# ET57.net
KiCad netlist of a schematic drawn in EAGLE
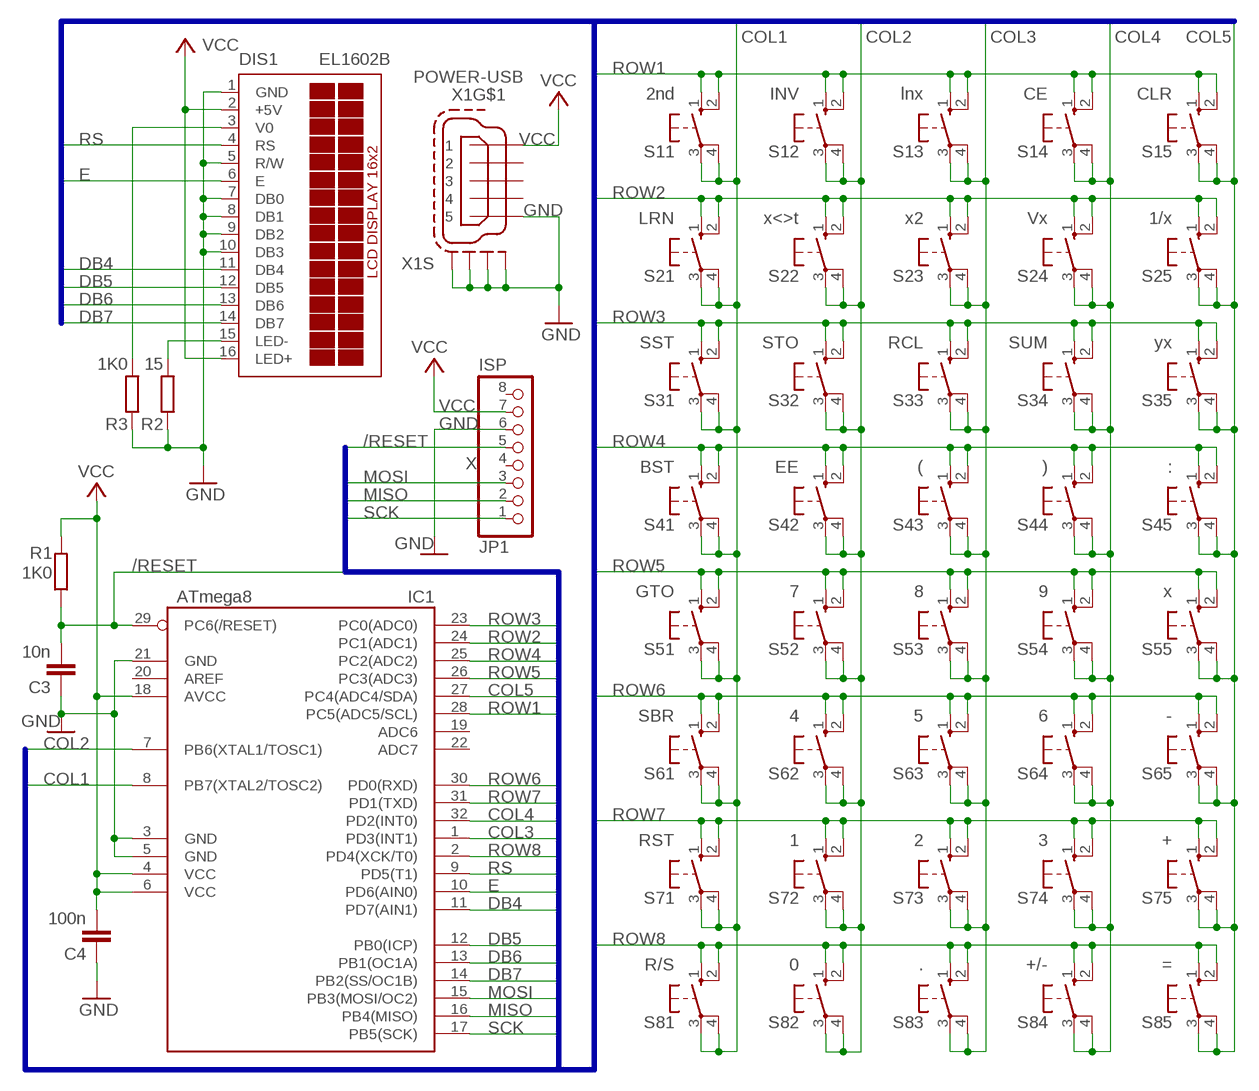
[diagram p0: schematic, sheet 1]

(export (version "E")
  (design (tool "Eeschema 10.0.6"))
  (components
    (comp (ref "C3")
      (value "10n")
      (footprint "eagle-import:C0805")
      (libsource (lib "eagle-import") (part "C-EUC0805"))
    )
    (comp (ref "C4")
      (value "100n")
      (footprint "eagle-import:C0805")
      (libsource (lib "eagle-import") (part "C-EUC0805"))
    )
    (comp (ref "DIS1")
      (value "EL1602B")
      (footprint "eagle-import:EL1602B")
      (libsource (lib "eagle-import") (part "EL1602B"))
    )
    (comp (ref "IC1")
      (value "ATmega8")
      (footprint "eagle-import:TQFP32-08")
      (fields (field (name "MPN") "ATMEGA8-16AU"))
      (libsource (lib "eagle-import") (part "MEGA8-AI"))
    )
    (comp (ref "JP1")
      (value "ISP")
      (footprint "eagle-import:1X08-BIG")
      (libsource (lib "eagle-import") (part "PINHD-1X8BIG"))
    )
    (comp (ref "R1")
      (value "1K0")
      (footprint "eagle-import:R0805")
      (libsource (lib "eagle-import") (part "R-EU_R0805"))
    )
    (comp (ref "R2")
      (value "15")
      (footprint "eagle-import:R0805")
      (libsource (lib "eagle-import") (part "R-EU_R0805"))
    )
    (comp (ref "R3")
      (value "1K0")
      (footprint "eagle-import:R0805")
      (libsource (lib "eagle-import") (part "R-EU_R0805"))
    )
    (comp (ref "S11")
      (value "2nd")
      (footprint "eagle-import:B3F-10XX")
      (fields (field (name "MPN") "B3F-1000"))
      (libsource (lib "eagle-import") (part "10-XX"))
    )
    (comp (ref "S12")
      (value "INV")
      (footprint "eagle-import:B3F-10XX")
      (fields (field (name "MPN") "B3F-1000"))
      (libsource (lib "eagle-import") (part "10-XX"))
    )
    (comp (ref "S13")
      (value "lnx")
      (footprint "eagle-import:B3F-10XX")
      (fields (field (name "MPN") "B3F-1000"))
      (libsource (lib "eagle-import") (part "10-XX"))
    )
    (comp (ref "S14")
      (value "CE")
      (footprint "eagle-import:B3F-10XX")
      (fields (field (name "MPN") "B3F-1000"))
      (libsource (lib "eagle-import") (part "10-XX"))
    )
    (comp (ref "S15")
      (value "CLR")
      (footprint "eagle-import:B3F-10XX")
      (fields (field (name "MPN") "B3F-1000"))
      (libsource (lib "eagle-import") (part "10-XX"))
    )
    (comp (ref "S21")
      (value "LRN")
      (footprint "eagle-import:B3F-10XX")
      (fields (field (name "MPN") "B3F-1000"))
      (libsource (lib "eagle-import") (part "10-XX"))
    )
    (comp (ref "S22")
      (value "x<>t")
      (footprint "eagle-import:B3F-10XX")
      (fields (field (name "MPN") "B3F-1000"))
      (libsource (lib "eagle-import") (part "10-XX"))
    )
    (comp (ref "S23")
      (value "x2")
      (footprint "eagle-import:B3F-10XX")
      (fields (field (name "MPN") "B3F-1000"))
      (libsource (lib "eagle-import") (part "10-XX"))
    )
    (comp (ref "S24")
      (value "Vx")
      (footprint "eagle-import:B3F-10XX")
      (fields (field (name "MPN") "B3F-1000"))
      (libsource (lib "eagle-import") (part "10-XX"))
    )
    (comp (ref "S25")
      (value "1/x")
      (footprint "eagle-import:B3F-10XX")
      (fields (field (name "MPN") "B3F-1000"))
      (libsource (lib "eagle-import") (part "10-XX"))
    )
    (comp (ref "S31")
      (value "SST")
      (footprint "eagle-import:B3F-10XX")
      (fields (field (name "MPN") "B3F-1000"))
      (libsource (lib "eagle-import") (part "10-XX"))
    )
    (comp (ref "S32")
      (value "STO")
      (footprint "eagle-import:B3F-10XX")
      (fields (field (name "MPN") "B3F-1000"))
      (libsource (lib "eagle-import") (part "10-XX"))
    )
    (comp (ref "S33")
      (value "RCL")
      (footprint "eagle-import:B3F-10XX")
      (fields (field (name "MPN") "B3F-1000"))
      (libsource (lib "eagle-import") (part "10-XX"))
    )
    (comp (ref "S34")
      (value "SUM")
      (footprint "eagle-import:B3F-10XX")
      (fields (field (name "MPN") "B3F-1000"))
      (libsource (lib "eagle-import") (part "10-XX"))
    )
    (comp (ref "S35")
      (value "yx")
      (footprint "eagle-import:B3F-10XX")
      (fields (field (name "MPN") "B3F-1000"))
      (libsource (lib "eagle-import") (part "10-XX"))
    )
    (comp (ref "S41")
      (value "BST")
      (footprint "eagle-import:B3F-10XX")
      (fields (field (name "MPN") "B3F-1000"))
      (libsource (lib "eagle-import") (part "10-XX"))
    )
    (comp (ref "S42")
      (value "EE")
      (footprint "eagle-import:B3F-10XX")
      (fields (field (name "MPN") "B3F-1000"))
      (libsource (lib "eagle-import") (part "10-XX"))
    )
    (comp (ref "S43")
      (value "(")
      (footprint "eagle-import:B3F-10XX")
      (fields (field (name "MPN") "B3F-1000"))
      (libsource (lib "eagle-import") (part "10-XX"))
    )
    (comp (ref "S44")
      (value ")")
      (footprint "eagle-import:B3F-10XX")
      (fields (field (name "MPN") "B3F-1000"))
      (libsource (lib "eagle-import") (part "10-XX"))
    )
    (comp (ref "S45")
      (value ":")
      (footprint "eagle-import:B3F-10XX")
      (fields (field (name "MPN") "B3F-1000"))
      (libsource (lib "eagle-import") (part "10-XX"))
    )
    (comp (ref "S51")
      (value "GTO")
      (footprint "eagle-import:B3F-10XX")
      (fields (field (name "MPN") "B3F-1000"))
      (libsource (lib "eagle-import") (part "10-XX"))
    )
    (comp (ref "S52")
      (value "7")
      (footprint "eagle-import:B3F-10XX")
      (fields (field (name "MPN") "B3F-1000"))
      (libsource (lib "eagle-import") (part "10-XX"))
    )
    (comp (ref "S53")
      (value "8")
      (footprint "eagle-import:B3F-10XX")
      (fields (field (name "MPN") "B3F-1000"))
      (libsource (lib "eagle-import") (part "10-XX"))
    )
    (comp (ref "S54")
      (value "9")
      (footprint "eagle-import:B3F-10XX")
      (fields (field (name "MPN") "B3F-1000"))
      (libsource (lib "eagle-import") (part "10-XX"))
    )
    (comp (ref "S55")
      (value "x")
      (footprint "eagle-import:B3F-10XX")
      (fields (field (name "MPN") "B3F-1000"))
      (libsource (lib "eagle-import") (part "10-XX"))
    )
    (comp (ref "S61")
      (value "SBR")
      (footprint "eagle-import:B3F-10XX")
      (fields (field (name "MPN") "B3F-1000"))
      (libsource (lib "eagle-import") (part "10-XX"))
    )
    (comp (ref "S62")
      (value "4")
      (footprint "eagle-import:B3F-10XX")
      (fields (field (name "MPN") "B3F-1000"))
      (libsource (lib "eagle-import") (part "10-XX"))
    )
    (comp (ref "S63")
      (value "5")
      (footprint "eagle-import:B3F-10XX")
      (fields (field (name "MPN") "B3F-1000"))
      (libsource (lib "eagle-import") (part "10-XX"))
    )
    (comp (ref "S64")
      (value "6")
      (footprint "eagle-import:B3F-10XX")
      (fields (field (name "MPN") "B3F-1000"))
      (libsource (lib "eagle-import") (part "10-XX"))
    )
    (comp (ref "S65")
      (value "-")
      (footprint "eagle-import:B3F-10XX")
      (fields (field (name "MPN") "B3F-1000"))
      (libsource (lib "eagle-import") (part "10-XX"))
    )
    (comp (ref "S71")
      (value "RST")
      (footprint "eagle-import:B3F-10XX")
      (fields (field (name "MPN") "B3F-1000"))
      (libsource (lib "eagle-import") (part "10-XX"))
    )
    (comp (ref "S72")
      (value "1")
      (footprint "eagle-import:B3F-10XX")
      (fields (field (name "MPN") "B3F-1000"))
      (libsource (lib "eagle-import") (part "10-XX"))
    )
    (comp (ref "S73")
      (value "2")
      (footprint "eagle-import:B3F-10XX")
      (fields (field (name "MPN") "B3F-1000"))
      (libsource (lib "eagle-import") (part "10-XX"))
    )
    (comp (ref "S74")
      (value "3")
      (footprint "eagle-import:B3F-10XX")
      (fields (field (name "MPN") "B3F-1000"))
      (libsource (lib "eagle-import") (part "10-XX"))
    )
    (comp (ref "S75")
      (value "+")
      (footprint "eagle-import:B3F-10XX")
      (fields (field (name "MPN") "B3F-1000"))
      (libsource (lib "eagle-import") (part "10-XX"))
    )
    (comp (ref "S81")
      (value "R/S")
      (footprint "eagle-import:B3F-10XX")
      (fields (field (name "MPN") "B3F-1000"))
      (libsource (lib "eagle-import") (part "10-XX"))
    )
    (comp (ref "S82")
      (value "0")
      (footprint "eagle-import:B3F-10XX")
      (fields (field (name "MPN") "B3F-1000"))
      (libsource (lib "eagle-import") (part "10-XX"))
    )
    (comp (ref "S83")
      (value ".")
      (footprint "eagle-import:B3F-10XX")
      (fields (field (name "MPN") "B3F-1000"))
      (libsource (lib "eagle-import") (part "10-XX"))
    )
    (comp (ref "S84")
      (value "+/-")
      (footprint "eagle-import:B3F-10XX")
      (fields (field (name "MPN") "B3F-1000"))
      (libsource (lib "eagle-import") (part "10-XX"))
    )
    (comp (ref "S85")
      (value "=")
      (footprint "eagle-import:B3F-10XX")
      (fields (field (name "MPN") "B3F-1000"))
      (libsource (lib "eagle-import") (part "10-XX"))
    )
    (comp (ref "X1")
      (value "POWER-USB")
      (footprint "eagle-import:32005-201")
      (libsource (lib "eagle-import") (part "MINI-USB-SCHIELD-32005-201"))
    )
  )
  (nets
    (net (code "1") (name "/COL1") (class "Default")
      (node (ref "IC1") (pin "8") (pinfunction "PB7(XTAL2/TOSC2)_8") (pintype "bidirectional"))
      (node (ref "S11") (pin "3") (pinfunction "P_3") (pintype "passive"))
      (node (ref "S11") (pin "4") (pinfunction "P1_4") (pintype "passive"))
      (node (ref "S21") (pin "3") (pinfunction "P_3") (pintype "passive"))
      (node (ref "S21") (pin "4") (pinfunction "P1_4") (pintype "passive"))
      (node (ref "S31") (pin "3") (pinfunction "P_3") (pintype "passive"))
      (node (ref "S31") (pin "4") (pinfunction "P1_4") (pintype "passive"))
      (node (ref "S41") (pin "3") (pinfunction "P_3") (pintype "passive"))
      (node (ref "S41") (pin "4") (pinfunction "P1_4") (pintype "passive"))
      (node (ref "S51") (pin "3") (pinfunction "P_3") (pintype "passive"))
      (node (ref "S51") (pin "4") (pinfunction "P1_4") (pintype "passive"))
      (node (ref "S61") (pin "3") (pinfunction "P_3") (pintype "passive"))
      (node (ref "S61") (pin "4") (pinfunction "P1_4") (pintype "passive"))
      (node (ref "S71") (pin "3") (pinfunction "P_3") (pintype "passive"))
      (node (ref "S71") (pin "4") (pinfunction "P1_4") (pintype "passive"))
      (node (ref "S81") (pin "3") (pinfunction "P_3") (pintype "passive"))
      (node (ref "S81") (pin "4") (pinfunction "P1_4") (pintype "passive"))
    )
    (net (code "2") (name "/COL2") (class "Default")
      (node (ref "IC1") (pin "7") (pinfunction "PB6(XTAL1/TOSC1)_7") (pintype "bidirectional"))
      (node (ref "S12") (pin "3") (pinfunction "P_3") (pintype "passive"))
      (node (ref "S12") (pin "4") (pinfunction "P1_4") (pintype "passive"))
      (node (ref "S22") (pin "3") (pinfunction "P_3") (pintype "passive"))
      (node (ref "S22") (pin "4") (pinfunction "P1_4") (pintype "passive"))
      (node (ref "S32") (pin "3") (pinfunction "P_3") (pintype "passive"))
      (node (ref "S32") (pin "4") (pinfunction "P1_4") (pintype "passive"))
      (node (ref "S42") (pin "3") (pinfunction "P_3") (pintype "passive"))
      (node (ref "S42") (pin "4") (pinfunction "P1_4") (pintype "passive"))
      (node (ref "S52") (pin "3") (pinfunction "P_3") (pintype "passive"))
      (node (ref "S52") (pin "4") (pinfunction "P1_4") (pintype "passive"))
      (node (ref "S62") (pin "3") (pinfunction "P_3") (pintype "passive"))
      (node (ref "S62") (pin "4") (pinfunction "P1_4") (pintype "passive"))
      (node (ref "S72") (pin "3") (pinfunction "P_3") (pintype "passive"))
      (node (ref "S72") (pin "4") (pinfunction "P1_4") (pintype "passive"))
      (node (ref "S82") (pin "3") (pinfunction "P_3") (pintype "passive"))
      (node (ref "S82") (pin "4") (pinfunction "P1_4") (pintype "passive"))
    )
    (net (code "3") (name "/COL3") (class "Default")
      (node (ref "IC1") (pin "1") (pinfunction "PD3(INT1)_1") (pintype "bidirectional"))
      (node (ref "S13") (pin "3") (pinfunction "P_3") (pintype "passive"))
      (node (ref "S13") (pin "4") (pinfunction "P1_4") (pintype "passive"))
      (node (ref "S23") (pin "3") (pinfunction "P_3") (pintype "passive"))
      (node (ref "S23") (pin "4") (pinfunction "P1_4") (pintype "passive"))
      (node (ref "S33") (pin "3") (pinfunction "P_3") (pintype "passive"))
      (node (ref "S33") (pin "4") (pinfunction "P1_4") (pintype "passive"))
      (node (ref "S43") (pin "3") (pinfunction "P_3") (pintype "passive"))
      (node (ref "S43") (pin "4") (pinfunction "P1_4") (pintype "passive"))
      (node (ref "S53") (pin "3") (pinfunction "P_3") (pintype "passive"))
      (node (ref "S53") (pin "4") (pinfunction "P1_4") (pintype "passive"))
      (node (ref "S63") (pin "3") (pinfunction "P_3") (pintype "passive"))
      (node (ref "S63") (pin "4") (pinfunction "P1_4") (pintype "passive"))
      (node (ref "S73") (pin "3") (pinfunction "P_3") (pintype "passive"))
      (node (ref "S73") (pin "4") (pinfunction "P1_4") (pintype "passive"))
      (node (ref "S83") (pin "3") (pinfunction "P_3") (pintype "passive"))
      (node (ref "S83") (pin "4") (pinfunction "P1_4") (pintype "passive"))
    )
    (net (code "4") (name "/COL4") (class "Default")
      (node (ref "IC1") (pin "32") (pinfunction "PD2(INT0)_32") (pintype "bidirectional"))
      (node (ref "S14") (pin "3") (pinfunction "P_3") (pintype "passive"))
      (node (ref "S14") (pin "4") (pinfunction "P1_4") (pintype "passive"))
      (node (ref "S24") (pin "3") (pinfunction "P_3") (pintype "passive"))
      (node (ref "S24") (pin "4") (pinfunction "P1_4") (pintype "passive"))
      (node (ref "S34") (pin "3") (pinfunction "P_3") (pintype "passive"))
      (node (ref "S34") (pin "4") (pinfunction "P1_4") (pintype "passive"))
      (node (ref "S44") (pin "3") (pinfunction "P_3") (pintype "passive"))
      (node (ref "S44") (pin "4") (pinfunction "P1_4") (pintype "passive"))
      (node (ref "S54") (pin "3") (pinfunction "P_3") (pintype "passive"))
      (node (ref "S54") (pin "4") (pinfunction "P1_4") (pintype "passive"))
      (node (ref "S64") (pin "3") (pinfunction "P_3") (pintype "passive"))
      (node (ref "S64") (pin "4") (pinfunction "P1_4") (pintype "passive"))
      (node (ref "S74") (pin "3") (pinfunction "P_3") (pintype "passive"))
      (node (ref "S74") (pin "4") (pinfunction "P1_4") (pintype "passive"))
      (node (ref "S84") (pin "3") (pinfunction "P_3") (pintype "passive"))
      (node (ref "S84") (pin "4") (pinfunction "P1_4") (pintype "passive"))
    )
    (net (code "5") (name "/COL5") (class "Default")
      (node (ref "IC1") (pin "27") (pinfunction "PC4(ADC4/SDA)_27") (pintype "bidirectional"))
      (node (ref "S15") (pin "3") (pinfunction "P_3") (pintype "passive"))
      (node (ref "S15") (pin "4") (pinfunction "P1_4") (pintype "passive"))
      (node (ref "S25") (pin "3") (pinfunction "P_3") (pintype "passive"))
      (node (ref "S25") (pin "4") (pinfunction "P1_4") (pintype "passive"))
      (node (ref "S35") (pin "3") (pinfunction "P_3") (pintype "passive"))
      (node (ref "S35") (pin "4") (pinfunction "P1_4") (pintype "passive"))
      (node (ref "S45") (pin "3") (pinfunction "P_3") (pintype "passive"))
      (node (ref "S45") (pin "4") (pinfunction "P1_4") (pintype "passive"))
      (node (ref "S55") (pin "3") (pinfunction "P_3") (pintype "passive"))
      (node (ref "S55") (pin "4") (pinfunction "P1_4") (pintype "passive"))
      (node (ref "S65") (pin "3") (pinfunction "P_3") (pintype "passive"))
      (node (ref "S65") (pin "4") (pinfunction "P1_4") (pintype "passive"))
      (node (ref "S75") (pin "3") (pinfunction "P_3") (pintype "passive"))
      (node (ref "S75") (pin "4") (pinfunction "P1_4") (pintype "passive"))
      (node (ref "S85") (pin "3") (pinfunction "P_3") (pintype "passive"))
      (node (ref "S85") (pin "4") (pinfunction "P1_4") (pintype "passive"))
    )
    (net (code "6") (name "/DB4") (class "Default")
      (node (ref "DIS1") (pin "11") (pinfunction "DB4_11") (pintype "input"))
      (node (ref "IC1") (pin "11") (pinfunction "PD7(AIN1)_11") (pintype "bidirectional"))
    )
    (net (code "7") (name "/DB5") (class "Default")
      (node (ref "DIS1") (pin "12") (pinfunction "DB5_12") (pintype "input"))
      (node (ref "IC1") (pin "12") (pinfunction "PB0(ICP)_12") (pintype "bidirectional"))
    )
    (net (code "8") (name "/DB6") (class "Default")
      (node (ref "DIS1") (pin "13") (pinfunction "DB6_13") (pintype "input"))
      (node (ref "IC1") (pin "13") (pinfunction "PB1(OC1A)_13") (pintype "bidirectional"))
    )
    (net (code "9") (name "/DB7") (class "Default")
      (node (ref "DIS1") (pin "14") (pinfunction "DB7_14") (pintype "input"))
      (node (ref "IC1") (pin "14") (pinfunction "PB2(SS/OC1B)_14") (pintype "bidirectional"))
    )
    (net (code "10") (name "/E") (class "Default")
      (node (ref "DIS1") (pin "6") (pinfunction "E_6") (pintype "input"))
      (node (ref "IC1") (pin "10") (pinfunction "PD6(AIN0)_10") (pintype "bidirectional"))
    )
    (net (code "11") (name "/MISO") (class "Default")
      (node (ref "IC1") (pin "16") (pinfunction "PB4(MISO)_16") (pintype "bidirectional"))
      (node (ref "JP1") (pin "2") (pinfunction "2_2") (pintype "passive"))
    )
    (net (code "12") (name "/MOSI") (class "Default")
      (node (ref "IC1") (pin "15") (pinfunction "PB3(MOSI/OC2)_15") (pintype "bidirectional"))
      (node (ref "JP1") (pin "3") (pinfunction "3_3") (pintype "passive"))
    )
    (net (code "13") (name "/ROW1") (class "Default")
      (node (ref "IC1") (pin "28") (pinfunction "PC5(ADC5/SCL)_28") (pintype "bidirectional"))
      (node (ref "S11") (pin "1") (pinfunction "S_1") (pintype "passive"))
      (node (ref "S11") (pin "2") (pinfunction "S1_2") (pintype "passive"))
      (node (ref "S12") (pin "1") (pinfunction "S_1") (pintype "passive"))
      (node (ref "S12") (pin "2") (pinfunction "S1_2") (pintype "passive"))
      (node (ref "S13") (pin "1") (pinfunction "S_1") (pintype "passive"))
      (node (ref "S13") (pin "2") (pinfunction "S1_2") (pintype "passive"))
      (node (ref "S14") (pin "1") (pinfunction "S_1") (pintype "passive"))
      (node (ref "S14") (pin "2") (pinfunction "S1_2") (pintype "passive"))
      (node (ref "S15") (pin "1") (pinfunction "S_1") (pintype "passive"))
      (node (ref "S15") (pin "2") (pinfunction "S1_2") (pintype "passive"))
    )
    (net (code "14") (name "/ROW2") (class "Default")
      (node (ref "IC1") (pin "24") (pinfunction "PC1(ADC1)_24") (pintype "bidirectional"))
      (node (ref "S21") (pin "1") (pinfunction "S_1") (pintype "passive"))
      (node (ref "S21") (pin "2") (pinfunction "S1_2") (pintype "passive"))
      (node (ref "S22") (pin "1") (pinfunction "S_1") (pintype "passive"))
      (node (ref "S22") (pin "2") (pinfunction "S1_2") (pintype "passive"))
      (node (ref "S23") (pin "1") (pinfunction "S_1") (pintype "passive"))
      (node (ref "S23") (pin "2") (pinfunction "S1_2") (pintype "passive"))
      (node (ref "S24") (pin "1") (pinfunction "S_1") (pintype "passive"))
      (node (ref "S24") (pin "2") (pinfunction "S1_2") (pintype "passive"))
      (node (ref "S25") (pin "1") (pinfunction "S_1") (pintype "passive"))
      (node (ref "S25") (pin "2") (pinfunction "S1_2") (pintype "passive"))
    )
    (net (code "15") (name "/ROW3") (class "Default")
      (node (ref "IC1") (pin "23") (pinfunction "PC0(ADC0)_23") (pintype "bidirectional"))
      (node (ref "S31") (pin "1") (pinfunction "S_1") (pintype "passive"))
      (node (ref "S31") (pin "2") (pinfunction "S1_2") (pintype "passive"))
      (node (ref "S32") (pin "1") (pinfunction "S_1") (pintype "passive"))
      (node (ref "S32") (pin "2") (pinfunction "S1_2") (pintype "passive"))
      (node (ref "S33") (pin "1") (pinfunction "S_1") (pintype "passive"))
      (node (ref "S33") (pin "2") (pinfunction "S1_2") (pintype "passive"))
      (node (ref "S34") (pin "1") (pinfunction "S_1") (pintype "passive"))
      (node (ref "S34") (pin "2") (pinfunction "S1_2") (pintype "passive"))
      (node (ref "S35") (pin "1") (pinfunction "S_1") (pintype "passive"))
      (node (ref "S35") (pin "2") (pinfunction "S1_2") (pintype "passive"))
    )
    (net (code "16") (name "/ROW4") (class "Default")
      (node (ref "IC1") (pin "25") (pinfunction "PC2(ADC2)_25") (pintype "bidirectional"))
      (node (ref "S41") (pin "1") (pinfunction "S_1") (pintype "passive"))
      (node (ref "S41") (pin "2") (pinfunction "S1_2") (pintype "passive"))
      (node (ref "S42") (pin "1") (pinfunction "S_1") (pintype "passive"))
      (node (ref "S42") (pin "2") (pinfunction "S1_2") (pintype "passive"))
      (node (ref "S43") (pin "1") (pinfunction "S_1") (pintype "passive"))
      (node (ref "S43") (pin "2") (pinfunction "S1_2") (pintype "passive"))
      (node (ref "S44") (pin "1") (pinfunction "S_1") (pintype "passive"))
      (node (ref "S44") (pin "2") (pinfunction "S1_2") (pintype "passive"))
      (node (ref "S45") (pin "1") (pinfunction "S_1") (pintype "passive"))
      (node (ref "S45") (pin "2") (pinfunction "S1_2") (pintype "passive"))
    )
    (net (code "17") (name "/ROW5") (class "Default")
      (node (ref "IC1") (pin "26") (pinfunction "PC3(ADC3)_26") (pintype "bidirectional"))
      (node (ref "S51") (pin "1") (pinfunction "S_1") (pintype "passive"))
      (node (ref "S51") (pin "2") (pinfunction "S1_2") (pintype "passive"))
      (node (ref "S52") (pin "1") (pinfunction "S_1") (pintype "passive"))
      (node (ref "S52") (pin "2") (pinfunction "S1_2") (pintype "passive"))
      (node (ref "S53") (pin "1") (pinfunction "S_1") (pintype "passive"))
      (node (ref "S53") (pin "2") (pinfunction "S1_2") (pintype "passive"))
      (node (ref "S54") (pin "1") (pinfunction "S_1") (pintype "passive"))
      (node (ref "S54") (pin "2") (pinfunction "S1_2") (pintype "passive"))
      (node (ref "S55") (pin "1") (pinfunction "S_1") (pintype "passive"))
      (node (ref "S55") (pin "2") (pinfunction "S1_2") (pintype "passive"))
    )
    (net (code "18") (name "/ROW6") (class "Default")
      (node (ref "IC1") (pin "30") (pinfunction "PD0(RXD)_30") (pintype "bidirectional"))
      (node (ref "S61") (pin "1") (pinfunction "S_1") (pintype "passive"))
      (node (ref "S61") (pin "2") (pinfunction "S1_2") (pintype "passive"))
      (node (ref "S62") (pin "1") (pinfunction "S_1") (pintype "passive"))
      (node (ref "S62") (pin "2") (pinfunction "S1_2") (pintype "passive"))
      (node (ref "S63") (pin "1") (pinfunction "S_1") (pintype "passive"))
      (node (ref "S63") (pin "2") (pinfunction "S1_2") (pintype "passive"))
      (node (ref "S64") (pin "1") (pinfunction "S_1") (pintype "passive"))
      (node (ref "S64") (pin "2") (pinfunction "S1_2") (pintype "passive"))
      (node (ref "S65") (pin "1") (pinfunction "S_1") (pintype "passive"))
      (node (ref "S65") (pin "2") (pinfunction "S1_2") (pintype "passive"))
    )
    (net (code "19") (name "/ROW7") (class "Default")
      (node (ref "IC1") (pin "31") (pinfunction "PD1(TXD)_31") (pintype "bidirectional"))
      (node (ref "S71") (pin "1") (pinfunction "S_1") (pintype "passive"))
      (node (ref "S71") (pin "2") (pinfunction "S1_2") (pintype "passive"))
      (node (ref "S72") (pin "1") (pinfunction "S_1") (pintype "passive"))
      (node (ref "S72") (pin "2") (pinfunction "S1_2") (pintype "passive"))
      (node (ref "S73") (pin "1") (pinfunction "S_1") (pintype "passive"))
      (node (ref "S73") (pin "2") (pinfunction "S1_2") (pintype "passive"))
      (node (ref "S74") (pin "1") (pinfunction "S_1") (pintype "passive"))
      (node (ref "S74") (pin "2") (pinfunction "S1_2") (pintype "passive"))
      (node (ref "S75") (pin "1") (pinfunction "S_1") (pintype "passive"))
      (node (ref "S75") (pin "2") (pinfunction "S1_2") (pintype "passive"))
    )
    (net (code "20") (name "/ROW8") (class "Default")
      (node (ref "IC1") (pin "2") (pinfunction "PD4(XCK/T0)_2") (pintype "bidirectional"))
      (node (ref "S81") (pin "1") (pinfunction "S_1") (pintype "passive"))
      (node (ref "S81") (pin "2") (pinfunction "S1_2") (pintype "passive"))
      (node (ref "S82") (pin "1") (pinfunction "S_1") (pintype "passive"))
      (node (ref "S82") (pin "2") (pinfunction "S1_2") (pintype "passive"))
      (node (ref "S83") (pin "1") (pinfunction "S_1") (pintype "passive"))
      (node (ref "S83") (pin "2") (pinfunction "S1_2") (pintype "passive"))
      (node (ref "S84") (pin "1") (pinfunction "S_1") (pintype "passive"))
      (node (ref "S84") (pin "2") (pinfunction "S1_2") (pintype "passive"))
      (node (ref "S85") (pin "1") (pinfunction "S_1") (pintype "passive"))
      (node (ref "S85") (pin "2") (pinfunction "S1_2") (pintype "passive"))
    )
    (net (code "21") (name "/RS") (class "Default")
      (node (ref "DIS1") (pin "4") (pinfunction "RS_4") (pintype "input"))
      (node (ref "IC1") (pin "9") (pinfunction "PD5(T1)_9") (pintype "bidirectional"))
    )
    (net (code "22") (name "/SCK") (class "Default")
      (node (ref "IC1") (pin "17") (pinfunction "PB5(SCK)_17") (pintype "bidirectional"))
      (node (ref "JP1") (pin "1") (pinfunction "1_1") (pintype "passive"))
    )
    (net (code "23") (name "/{slash}RESET") (class "Default")
      (node (ref "C3") (pin "2") (pinfunction "2_2") (pintype "passive"))
      (node (ref "IC1") (pin "29") (pinfunction "PC6(/RESET)_29") (pintype "bidirectional"))
      (node (ref "JP1") (pin "5") (pinfunction "5_5") (pintype "passive"))
      (node (ref "R1") (pin "1") (pinfunction "1_1") (pintype "passive"))
    )
    (net (code "24") (name "GND") (class "Default")
      (node (ref "C3") (pin "1") (pinfunction "1_1") (pintype "passive"))
      (node (ref "C4") (pin "1") (pinfunction "1_1") (pintype "passive"))
      (node (ref "DIS1") (pin "1") (pinfunction "GND_1") (pintype "power_in"))
      (node (ref "DIS1") (pin "10") (pinfunction "DB3_10") (pintype "input"))
      (node (ref "DIS1") (pin "5") (pinfunction "R/W_5") (pintype "input"))
      (node (ref "DIS1") (pin "7") (pinfunction "DB0_7") (pintype "input"))
      (node (ref "DIS1") (pin "8") (pinfunction "DB1_8") (pintype "input"))
      (node (ref "DIS1") (pin "9") (pinfunction "DB2_9") (pintype "input"))
      (node (ref "IC1") (pin "21") (pinfunction "GND_21") (pintype "power_in"))
      (node (ref "IC1") (pin "3") (pinfunction "GND_3") (pintype "power_in"))
      (node (ref "IC1") (pin "5") (pinfunction "GND_5") (pintype "power_in"))
      (node (ref "JP1") (pin "6") (pinfunction "6_6") (pintype "passive"))
      (node (ref "R2") (pin "1") (pinfunction "1_1") (pintype "passive"))
      (node (ref "R3") (pin "1") (pinfunction "1_1") (pintype "passive"))
      (node (ref "X1") (pin "5") (pinfunction "5_5") (pintype "passive"))
      (node (ref "X1") (pin "M1") (pinfunction "S1_M1") (pintype "passive"))
      (node (ref "X1") (pin "M2") (pinfunction "S2_M2") (pintype "passive"))
      (node (ref "X1") (pin "M3") (pinfunction "S3_M3") (pintype "passive"))
      (node (ref "X1") (pin "M4") (pinfunction "S4_M4") (pintype "passive"))
    )
    (net (code "25") (name "Net-(DIS1-LED-)") (class "Default")
      (node (ref "DIS1") (pin "15") (pinfunction "LED-_15") (pintype "bidirectional"))
      (node (ref "R2") (pin "2") (pinfunction "2_2") (pintype "passive"))
    )
    (net (code "26") (name "Net-(DIS1-V0)") (class "Default")
      (node (ref "DIS1") (pin "3") (pinfunction "V0_3") (pintype "input"))
      (node (ref "R3") (pin "2") (pinfunction "2_2") (pintype "passive"))
    )
    (net (code "27") (name "VCC") (class "Default")
      (node (ref "C4") (pin "2") (pinfunction "2_2") (pintype "passive"))
      (node (ref "DIS1") (pin "16") (pinfunction "LED+_16") (pintype "bidirectional"))
      (node (ref "DIS1") (pin "2") (pinfunction "+5V_2") (pintype "power_in"))
      (node (ref "IC1") (pin "18") (pinfunction "AVCC_18") (pintype "power_in"))
      (node (ref "IC1") (pin "4") (pinfunction "VCC_4") (pintype "power_in"))
      (node (ref "IC1") (pin "6") (pinfunction "VCC_6") (pintype "power_in"))
      (node (ref "JP1") (pin "7") (pinfunction "7_7") (pintype "passive"))
      (node (ref "R1") (pin "2") (pinfunction "2_2") (pintype "passive"))
      (node (ref "X1") (pin "1") (pinfunction "1_1") (pintype "passive"))
    )
    (net (code "28") (name "unconnected-(IC1-ADC6-Pad19)") (class "Default")
      (node (ref "IC1") (pin "19") (pinfunction "ADC6_19") (pintype "bidirectional"))
    )
    (net (code "29") (name "unconnected-(IC1-ADC7-Pad22)") (class "Default")
      (node (ref "IC1") (pin "22") (pinfunction "ADC7_22") (pintype "bidirectional"))
    )
    (net (code "30") (name "unconnected-(IC1-AREF-Pad20)") (class "Default")
      (node (ref "IC1") (pin "20") (pinfunction "AREF_20") (pintype "passive"))
    )
    (net (code "31") (name "unconnected-(JP1-Pad4)") (class "Default")
      (node (ref "JP1") (pin "4") (pinfunction "4_4") (pintype "passive"))
    )
    (net (code "32") (name "unconnected-(JP1-Pad8)") (class "Default")
      (node (ref "JP1") (pin "8") (pinfunction "8_8") (pintype "passive"))
    )
    (net (code "33") (name "unconnected-(X1-Pad2)") (class "Default")
      (node (ref "X1") (pin "2") (pinfunction "2_2") (pintype "passive"))
    )
    (net (code "34") (name "unconnected-(X1-Pad3)") (class "Default")
      (node (ref "X1") (pin "3") (pinfunction "3_3") (pintype "passive"))
    )
    (net (code "35") (name "unconnected-(X1-Pad4)") (class "Default")
      (node (ref "X1") (pin "4") (pinfunction "4_4") (pintype "passive"))
    )
  )
)
